# pressure_flow.net
KiCad netlist of a schematic drawn in EAGLE
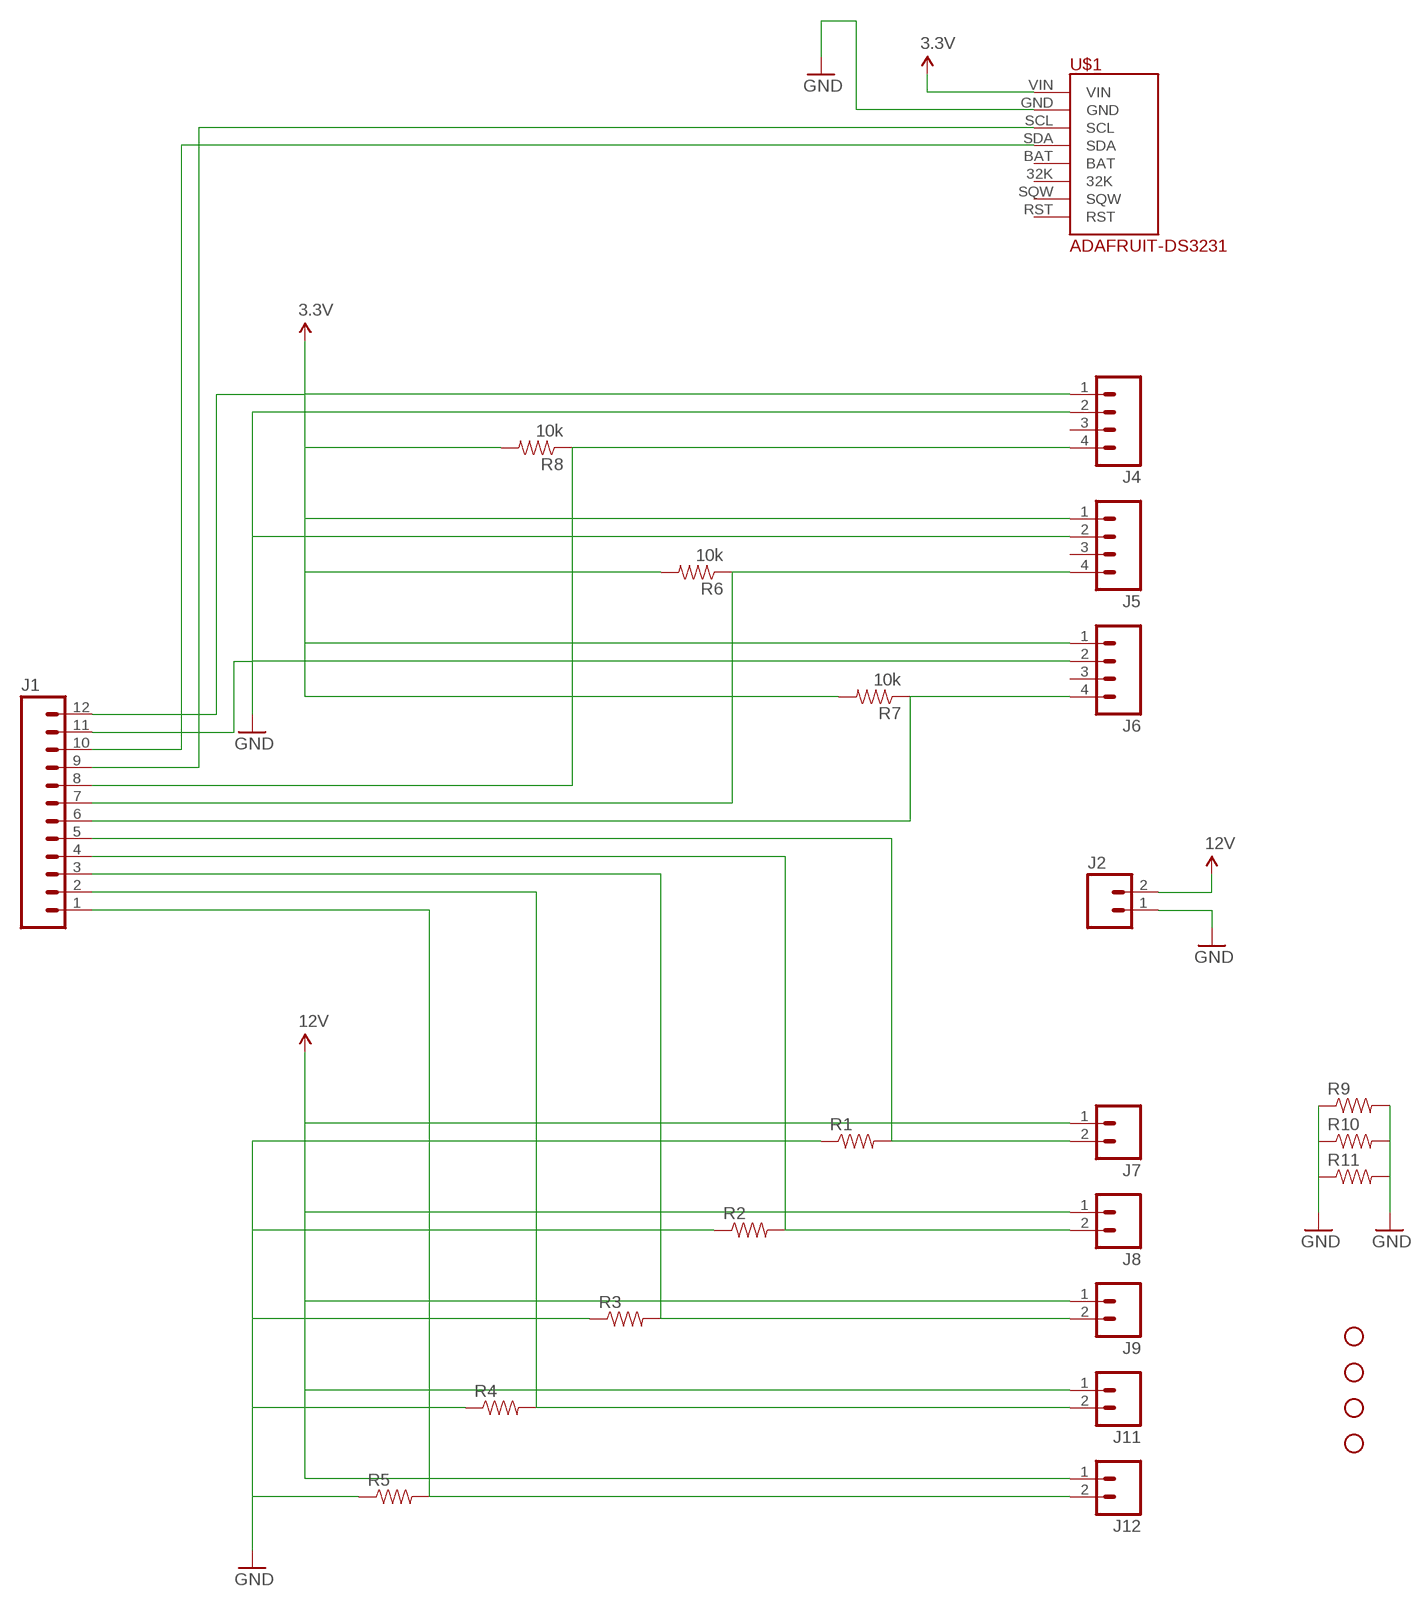
[diagram p0: schematic, sheet 1]

(export (version "E")
  (design (tool "Eeschema 10.0.6"))
  (components
    (comp (ref "H1")
      (value "STAND-OFF")
      (footprint "eagle-import:STAND-OFF")
      (libsource (lib "eagle-import") (part "STAND-OFF"))
    )
    (comp (ref "H2")
      (value "STAND-OFF")
      (footprint "eagle-import:STAND-OFF")
      (libsource (lib "eagle-import") (part "STAND-OFF"))
    )
    (comp (ref "H3")
      (value "STAND-OFF")
      (footprint "eagle-import:STAND-OFF")
      (libsource (lib "eagle-import") (part "STAND-OFF"))
    )
    (comp (ref "H4")
      (value "STAND-OFF")
      (footprint "eagle-import:STAND-OFF")
      (libsource (lib "eagle-import") (part "STAND-OFF"))
    )
    (comp (ref "J1")
      (value "M12LOCK_LONGPADS")
      (footprint "eagle-import:1X12_LOCK_LONGPADS")
      (libsource (lib "eagle-import") (part "M12LOCK_LONGPADS"))
    )
    (comp (ref "J2")
      (value "M02LOCK_LONGPADS")
      (footprint "eagle-import:1X02_LOCK_LONGPADS")
      (libsource (lib "eagle-import") (part "M02LOCK_LONGPADS"))
    )
    (comp (ref "J4")
      (value "M04LOCK_LONGPADS")
      (footprint "eagle-import:1X04_LOCK_LONGPADS")
      (libsource (lib "eagle-import") (part "M04LOCK_LONGPADS"))
    )
    (comp (ref "J5")
      (value "M04LOCK_LONGPADS")
      (footprint "eagle-import:1X04_LOCK_LONGPADS")
      (libsource (lib "eagle-import") (part "M04LOCK_LONGPADS"))
    )
    (comp (ref "J6")
      (value "M04LOCK_LONGPADS")
      (footprint "eagle-import:1X04_LOCK_LONGPADS")
      (libsource (lib "eagle-import") (part "M04LOCK_LONGPADS"))
    )
    (comp (ref "J7")
      (value "M02LOCK_LONGPADS")
      (footprint "eagle-import:1X02_LOCK_LONGPADS")
      (libsource (lib "eagle-import") (part "M02LOCK_LONGPADS"))
    )
    (comp (ref "J8")
      (value "M02LOCK_LONGPADS")
      (footprint "eagle-import:1X02_LOCK_LONGPADS")
      (libsource (lib "eagle-import") (part "M02LOCK_LONGPADS"))
    )
    (comp (ref "J9")
      (value "M02LOCK_LONGPADS")
      (footprint "eagle-import:1X02_LOCK_LONGPADS")
      (libsource (lib "eagle-import") (part "M02LOCK_LONGPADS"))
    )
    (comp (ref "J11")
      (value "M02LOCK_LONGPADS")
      (footprint "eagle-import:1X02_LOCK_LONGPADS")
      (libsource (lib "eagle-import") (part "M02LOCK_LONGPADS"))
    )
    (comp (ref "J12")
      (value "M02LOCK_LONGPADS")
      (footprint "eagle-import:1X02_LOCK_LONGPADS")
      (libsource (lib "eagle-import") (part "M02LOCK_LONGPADS"))
    )
    (comp (ref "R1")
      (value "RESISTORPTH-1/2W")
      (footprint "eagle-import:AXIAL-0.5")
      (libsource (lib "eagle-import") (part "RESISTORPTH-1/2W"))
    )
    (comp (ref "R2")
      (value "RESISTORPTH-1/2W")
      (footprint "eagle-import:AXIAL-0.5")
      (libsource (lib "eagle-import") (part "RESISTORPTH-1/2W"))
    )
    (comp (ref "R3")
      (value "RESISTORPTH-1/2W")
      (footprint "eagle-import:AXIAL-0.5")
      (libsource (lib "eagle-import") (part "RESISTORPTH-1/2W"))
    )
    (comp (ref "R4")
      (value "RESISTORPTH-1/2W")
      (footprint "eagle-import:AXIAL-0.5")
      (libsource (lib "eagle-import") (part "RESISTORPTH-1/2W"))
    )
    (comp (ref "R5")
      (value "RESISTORPTH-1/2W")
      (footprint "eagle-import:AXIAL-0.5")
      (libsource (lib "eagle-import") (part "RESISTORPTH-1/2W"))
    )
    (comp (ref "R6")
      (value "10k")
      (footprint "eagle-import:AXIAL-0.3")
      (libsource (lib "eagle-import") (part "10KOHM-1/4W-1%(PTH)HORIZ"))
    )
    (comp (ref "R7")
      (value "10k")
      (footprint "eagle-import:AXIAL-0.3")
      (libsource (lib "eagle-import") (part "10KOHM-1/4W-1%(PTH)HORIZ"))
    )
    (comp (ref "R8")
      (value "10k")
      (footprint "eagle-import:AXIAL-0.3")
      (libsource (lib "eagle-import") (part "10KOHM-1/4W-1%(PTH)HORIZ"))
    )
    (comp (ref "R9")
      (value "RESISTORPTH-1/2W")
      (footprint "eagle-import:AXIAL-0.5")
      (libsource (lib "eagle-import") (part "RESISTORPTH-1/2W"))
    )
    (comp (ref "R10")
      (value "RESISTORPTH-1/2W")
      (footprint "eagle-import:AXIAL-0.5")
      (libsource (lib "eagle-import") (part "RESISTORPTH-1/2W"))
    )
    (comp (ref "R11")
      (value "RESISTORPTH-1/2W")
      (footprint "eagle-import:AXIAL-0.5")
      (libsource (lib "eagle-import") (part "RESISTORPTH-1/2W"))
    )
    (comp (ref "U$1")
      (value "ADAFRUIT-DS3231")
      (footprint "eagle-import:ADAFRUIT-DS3231")
      (libsource (lib "eagle-import") (part "ADAFRUIT-DS3231"))
    )
  )
  (nets
    (net (code "1") (name "3.3V") (class "Default")
      (node (ref "J1") (pin "12") (pinfunction "12_12") (pintype "passive"))
      (node (ref "J4") (pin "1") (pinfunction "1_1") (pintype "passive"))
      (node (ref "J5") (pin "1") (pinfunction "1_1") (pintype "passive"))
      (node (ref "J6") (pin "1") (pinfunction "1_1") (pintype "passive"))
      (node (ref "R6") (pin "P$2") (pinfunction "2_P$2") (pintype "passive"))
      (node (ref "R7") (pin "P$2") (pinfunction "2_P$2") (pintype "passive"))
      (node (ref "R8") (pin "P$2") (pinfunction "2_P$2") (pintype "passive"))
      (node (ref "U$1") (pin "VIN") (pinfunction "VIN_VIN") (pintype "bidirectional"))
    )
    (net (code "2") (name "12V") (class "Default")
      (node (ref "J11") (pin "1") (pinfunction "1_1") (pintype "passive"))
      (node (ref "J12") (pin "1") (pinfunction "1_1") (pintype "passive"))
      (node (ref "J2") (pin "2") (pinfunction "2_2") (pintype "passive"))
      (node (ref "J7") (pin "1") (pinfunction "1_1") (pintype "passive"))
      (node (ref "J8") (pin "1") (pinfunction "1_1") (pintype "passive"))
      (node (ref "J9") (pin "1") (pinfunction "1_1") (pintype "passive"))
    )
    (net (code "3") (name "GND") (class "Default")
      (node (ref "J1") (pin "11") (pinfunction "11_11") (pintype "passive"))
      (node (ref "J2") (pin "1") (pinfunction "1_1") (pintype "passive"))
      (node (ref "J4") (pin "2") (pinfunction "2_2") (pintype "passive"))
      (node (ref "J5") (pin "2") (pinfunction "2_2") (pintype "passive"))
      (node (ref "J6") (pin "2") (pinfunction "2_2") (pintype "passive"))
      (node (ref "R1") (pin "P$1") (pinfunction "1_P$1") (pintype "passive"))
      (node (ref "R10") (pin "P$1") (pinfunction "1_P$1") (pintype "passive"))
      (node (ref "R10") (pin "P$2") (pinfunction "2_P$2") (pintype "passive"))
      (node (ref "R11") (pin "P$1") (pinfunction "1_P$1") (pintype "passive"))
      (node (ref "R11") (pin "P$2") (pinfunction "2_P$2") (pintype "passive"))
      (node (ref "R2") (pin "P$1") (pinfunction "1_P$1") (pintype "passive"))
      (node (ref "R3") (pin "P$1") (pinfunction "1_P$1") (pintype "passive"))
      (node (ref "R4") (pin "P$1") (pinfunction "1_P$1") (pintype "passive"))
      (node (ref "R5") (pin "P$1") (pinfunction "1_P$1") (pintype "passive"))
      (node (ref "R9") (pin "P$1") (pinfunction "1_P$1") (pintype "passive"))
      (node (ref "R9") (pin "P$2") (pinfunction "2_P$2") (pintype "passive"))
      (node (ref "U$1") (pin "GND") (pinfunction "GND_GND") (pintype "bidirectional"))
    )
    (net (code "4") (name "Net-(J1-Pad9)") (class "Default")
      (node (ref "J1") (pin "9") (pinfunction "9_9") (pintype "passive"))
      (node (ref "U$1") (pin "SCL") (pinfunction "SCL_SCL") (pintype "bidirectional"))
    )
    (net (code "5") (name "Net-(J1-Pad10)") (class "Default")
      (node (ref "J1") (pin "10") (pinfunction "10_10") (pintype "passive"))
      (node (ref "U$1") (pin "SDA") (pinfunction "SDA_SDA") (pintype "bidirectional"))
    )
    (net (code "6") (name "Net-(R1-2)") (class "Default")
      (node (ref "J1") (pin "5") (pinfunction "5_5") (pintype "passive"))
      (node (ref "J7") (pin "2") (pinfunction "2_2") (pintype "passive"))
      (node (ref "R1") (pin "P$2") (pinfunction "2_P$2") (pintype "passive"))
    )
    (net (code "7") (name "Net-(R2-2)") (class "Default")
      (node (ref "J1") (pin "4") (pinfunction "4_4") (pintype "passive"))
      (node (ref "J8") (pin "2") (pinfunction "2_2") (pintype "passive"))
      (node (ref "R2") (pin "P$2") (pinfunction "2_P$2") (pintype "passive"))
    )
    (net (code "8") (name "Net-(R3-2)") (class "Default")
      (node (ref "J1") (pin "3") (pinfunction "3_3") (pintype "passive"))
      (node (ref "J9") (pin "2") (pinfunction "2_2") (pintype "passive"))
      (node (ref "R3") (pin "P$2") (pinfunction "2_P$2") (pintype "passive"))
    )
    (net (code "9") (name "Net-(R4-2)") (class "Default")
      (node (ref "J1") (pin "2") (pinfunction "2_2") (pintype "passive"))
      (node (ref "J11") (pin "2") (pinfunction "2_2") (pintype "passive"))
      (node (ref "R4") (pin "P$2") (pinfunction "2_P$2") (pintype "passive"))
    )
    (net (code "10") (name "Net-(R5-2)") (class "Default")
      (node (ref "J1") (pin "1") (pinfunction "1_1") (pintype "passive"))
      (node (ref "J12") (pin "2") (pinfunction "2_2") (pintype "passive"))
      (node (ref "R5") (pin "P$2") (pinfunction "2_P$2") (pintype "passive"))
    )
    (net (code "11") (name "Net-(R6-1)") (class "Default")
      (node (ref "J1") (pin "7") (pinfunction "7_7") (pintype "passive"))
      (node (ref "J5") (pin "4") (pinfunction "4_4") (pintype "passive"))
      (node (ref "R6") (pin "P$1") (pinfunction "1_P$1") (pintype "passive"))
    )
    (net (code "12") (name "Net-(R7-1)") (class "Default")
      (node (ref "J1") (pin "6") (pinfunction "6_6") (pintype "passive"))
      (node (ref "J6") (pin "4") (pinfunction "4_4") (pintype "passive"))
      (node (ref "R7") (pin "P$1") (pinfunction "1_P$1") (pintype "passive"))
    )
    (net (code "13") (name "Net-(R8-1)") (class "Default")
      (node (ref "J1") (pin "8") (pinfunction "8_8") (pintype "passive"))
      (node (ref "J4") (pin "4") (pinfunction "4_4") (pintype "passive"))
      (node (ref "R8") (pin "P$1") (pinfunction "1_P$1") (pintype "passive"))
    )
    (net (code "14") (name "unconnected-(J4-Pad3)") (class "Default")
      (node (ref "J4") (pin "3") (pinfunction "3_3") (pintype "passive"))
    )
    (net (code "15") (name "unconnected-(J5-Pad3)") (class "Default")
      (node (ref "J5") (pin "3") (pinfunction "3_3") (pintype "passive"))
    )
    (net (code "16") (name "unconnected-(J6-Pad3)") (class "Default")
      (node (ref "J6") (pin "3") (pinfunction "3_3") (pintype "passive"))
    )
    (net (code "17") (name "unconnected-(U$1-Pad32K)") (class "Default")
      (node (ref "U$1") (pin "32K") (pinfunction "32K_32K") (pintype "bidirectional"))
    )
    (net (code "18") (name "unconnected-(U$1-PadBAT)") (class "Default")
      (node (ref "U$1") (pin "BAT") (pinfunction "BAT_BAT") (pintype "bidirectional"))
    )
    (net (code "19") (name "unconnected-(U$1-PadRST)") (class "Default")
      (node (ref "U$1") (pin "RST") (pinfunction "RST_RST") (pintype "bidirectional"))
    )
    (net (code "20") (name "unconnected-(U$1-PadSQW)") (class "Default")
      (node (ref "U$1") (pin "SQW") (pinfunction "SQW_SQW") (pintype "bidirectional"))
    )
  )
)
